# controller.net
KiCad netlist of a schematic drawn in EAGLE
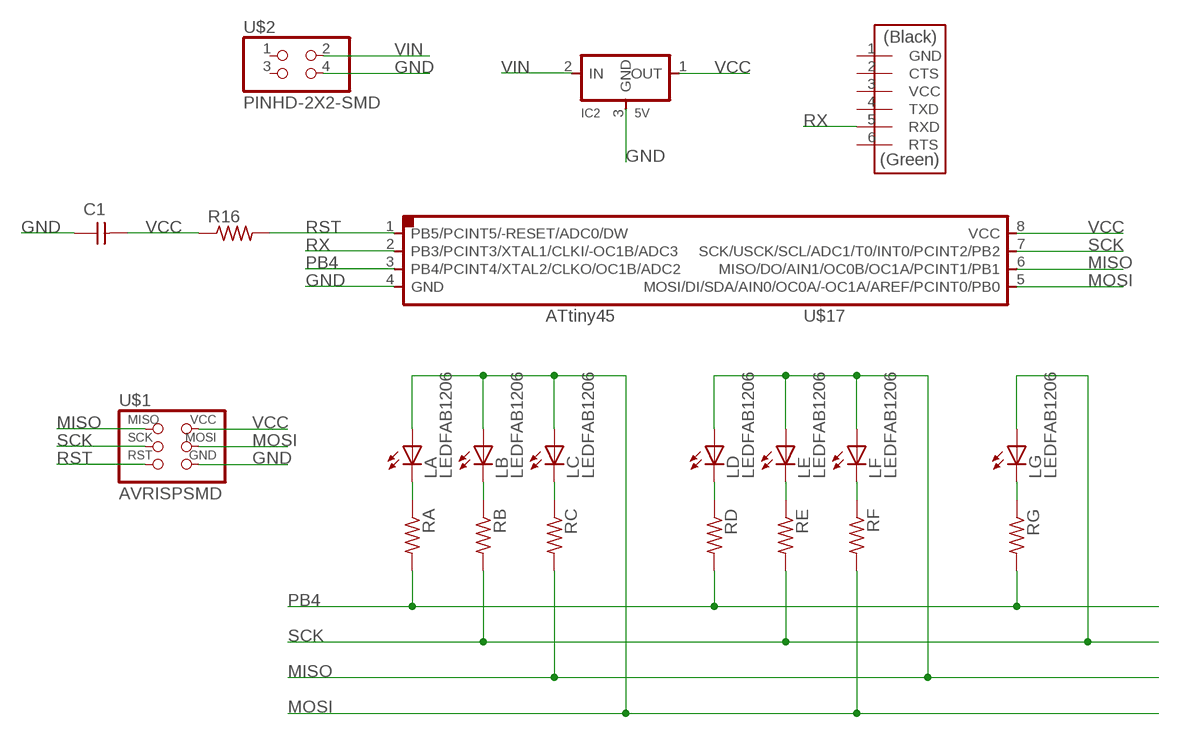
[diagram p0: schematic, sheet 1]

(export (version "E")
  (design (tool "Eeschema 10.0.6"))
  (components
    (comp (ref "C1")
      (value "CAP-UNPOLARIZEDFAB")
      (footprint "eagle-import:C1206FAB")
      (libsource (lib "eagle-import") (part "CAP-UNPOLARIZEDFAB"))
    )
    (comp (ref "IC2")
      (value "5V")
      (footprint "eagle-import:SOT23")
      (libsource (lib "eagle-import") (part "REGULATORSOT23"))
    )
    (comp (ref "LA")
      (value "LEDFAB1206")
      (footprint "eagle-import:LED1206FAB")
      (libsource (lib "eagle-import") (part "LEDFAB1206"))
    )
    (comp (ref "LB")
      (value "LEDFAB1206")
      (footprint "eagle-import:LED1206FAB")
      (libsource (lib "eagle-import") (part "LEDFAB1206"))
    )
    (comp (ref "LC")
      (value "LEDFAB1206")
      (footprint "eagle-import:LED1206FAB")
      (libsource (lib "eagle-import") (part "LEDFAB1206"))
    )
    (comp (ref "LD")
      (value "LEDFAB1206")
      (footprint "eagle-import:LED1206FAB")
      (libsource (lib "eagle-import") (part "LEDFAB1206"))
    )
    (comp (ref "LE")
      (value "LEDFAB1206")
      (footprint "eagle-import:LED1206FAB")
      (libsource (lib "eagle-import") (part "LEDFAB1206"))
    )
    (comp (ref "LF")
      (value "LEDFAB1206")
      (footprint "eagle-import:LED1206FAB")
      (libsource (lib "eagle-import") (part "LEDFAB1206"))
    )
    (comp (ref "LG")
      (value "LEDFAB1206")
      (footprint "eagle-import:LED1206FAB")
      (libsource (lib "eagle-import") (part "LEDFAB1206"))
    )
    (comp (ref "R16")
      (value "RES-US1206FAB")
      (footprint "eagle-import:R1206FAB")
      (libsource (lib "eagle-import") (part "RES-US1206FAB"))
    )
    (comp (ref "RA")
      (value "RES-US1206FAB")
      (footprint "eagle-import:R1206FAB")
      (libsource (lib "eagle-import") (part "RES-US1206FAB"))
    )
    (comp (ref "RB")
      (value "RES-US1206FAB")
      (footprint "eagle-import:R1206FAB")
      (libsource (lib "eagle-import") (part "RES-US1206FAB"))
    )
    (comp (ref "RC")
      (value "RES-US1206FAB")
      (footprint "eagle-import:R1206FAB")
      (libsource (lib "eagle-import") (part "RES-US1206FAB"))
    )
    (comp (ref "RD")
      (value "RES-US1206FAB")
      (footprint "eagle-import:R1206FAB")
      (libsource (lib "eagle-import") (part "RES-US1206FAB"))
    )
    (comp (ref "RE")
      (value "RES-US1206FAB")
      (footprint "eagle-import:R1206FAB")
      (libsource (lib "eagle-import") (part "RES-US1206FAB"))
    )
    (comp (ref "RF")
      (value "RES-US1206FAB")
      (footprint "eagle-import:R1206FAB")
      (libsource (lib "eagle-import") (part "RES-US1206FAB"))
    )
    (comp (ref "RG")
      (value "RES-US1206FAB")
      (footprint "eagle-import:R1206FAB")
      (libsource (lib "eagle-import") (part "RES-US1206FAB"))
    )
    (comp (ref "U$1")
      (value "AVRISPSMD")
      (footprint "eagle-import:2X03SMD")
      (libsource (lib "eagle-import") (part "AVRISPSMD"))
    )
    (comp (ref "U$2")
      (value "PINHD-2X2-SMD")
      (footprint "eagle-import:2X02SMD")
      (libsource (lib "eagle-import") (part "PINHD-2X2-SMD"))
    )
    (comp (ref "U$3")
      (value "FTDI-SMD-HEADER")
      (footprint "eagle-import:1X06SMD")
      (libsource (lib "eagle-import") (part "FTDI-SMD-HEADER"))
    )
    (comp (ref "U$17")
      (value "ATTINY45SI")
      (footprint "eagle-import:SOIC8")
      (libsource (lib "eagle-import") (part "ATTINY45SI"))
    )
  )
  (nets
    (net (code "1") (name "/GND") (class "Default")
      (node (ref "C1") (pin "1") (pinfunction "1_1") (pintype "passive"))
      (node (ref "IC2") (pin "3") (pinfunction "GND_3") (pintype "bidirectional"))
      (node (ref "U$1") (pin "6") (pinfunction "GND_6") (pintype "passive"))
      (node (ref "U$17") (pin "4") (pinfunction "GND_4") (pintype "bidirectional"))
      (node (ref "U$2") (pin "4") (pinfunction "4_4") (pintype "passive"))
    )
    (net (code "2") (name "/MISO") (class "Default")
      (node (ref "LD") (pin "1") (pinfunction "A_1") (pintype "passive"))
      (node (ref "LE") (pin "1") (pinfunction "A_1") (pintype "passive"))
      (node (ref "LF") (pin "1") (pinfunction "A_1") (pintype "passive"))
      (node (ref "RC") (pin "2") (pinfunction "2_2") (pintype "passive"))
      (node (ref "U$1") (pin "1") (pinfunction "MISO_1") (pintype "passive"))
      (node (ref "U$17") (pin "6") (pinfunction "MISO/DO/AIN1/OC0B/OC1A/PCINT1/PB1_6") (pintype "bidirectional"))
    )
    (net (code "3") (name "/MOSI") (class "Default")
      (node (ref "LA") (pin "1") (pinfunction "A_1") (pintype "passive"))
      (node (ref "LB") (pin "1") (pinfunction "A_1") (pintype "passive"))
      (node (ref "LC") (pin "1") (pinfunction "A_1") (pintype "passive"))
      (node (ref "RF") (pin "2") (pinfunction "2_2") (pintype "passive"))
      (node (ref "U$1") (pin "4") (pinfunction "MOSI_4") (pintype "passive"))
      (node (ref "U$17") (pin "5") (pinfunction "MOSI/DI/SDA/AIN0/OC0A/-OC1A/AREF/PCINT0/PB0_5") (pintype "bidirectional"))
    )
    (net (code "4") (name "/PB4") (class "Default")
      (node (ref "RA") (pin "2") (pinfunction "2_2") (pintype "passive"))
      (node (ref "RD") (pin "2") (pinfunction "2_2") (pintype "passive"))
      (node (ref "RG") (pin "2") (pinfunction "2_2") (pintype "passive"))
      (node (ref "U$17") (pin "3") (pinfunction "PB4/PCINT4/XTAL2/CLKO/OC1B/ADC2_3") (pintype "bidirectional"))
    )
    (net (code "5") (name "/RST") (class "Default")
      (node (ref "R16") (pin "2") (pinfunction "2_2") (pintype "passive"))
      (node (ref "U$1") (pin "5") (pinfunction "RST_5") (pintype "passive"))
      (node (ref "U$17") (pin "1") (pinfunction "PB5/PCINT5/-RESET/ADC0/DW_1") (pintype "bidirectional"))
    )
    (net (code "6") (name "/RX") (class "Default")
      (node (ref "U$17") (pin "2") (pinfunction "PB3/PCINT3/XTAL1/CLKI/-OC1B/ADC3_2") (pintype "bidirectional"))
      (node (ref "U$3") (pin "5") (pinfunction "RXD_5") (pintype "bidirectional"))
    )
    (net (code "7") (name "/SCK") (class "Default")
      (node (ref "LG") (pin "1") (pinfunction "A_1") (pintype "passive"))
      (node (ref "RB") (pin "2") (pinfunction "2_2") (pintype "passive"))
      (node (ref "RE") (pin "2") (pinfunction "2_2") (pintype "passive"))
      (node (ref "U$1") (pin "3") (pinfunction "SCK_3") (pintype "passive"))
      (node (ref "U$17") (pin "7") (pinfunction "SCK/USCK/SCL/ADC1/T0/INT0/PCINT2/PB2_7") (pintype "bidirectional"))
    )
    (net (code "8") (name "/VCC") (class "Default")
      (node (ref "C1") (pin "2") (pinfunction "2_2") (pintype "passive"))
      (node (ref "IC2") (pin "1") (pinfunction "OUT_1") (pintype "bidirectional"))
      (node (ref "R16") (pin "1") (pinfunction "1_1") (pintype "passive"))
      (node (ref "U$1") (pin "2") (pinfunction "VCC_2") (pintype "passive"))
      (node (ref "U$17") (pin "8") (pinfunction "VCC_8") (pintype "bidirectional"))
    )
    (net (code "9") (name "/VIN") (class "Default")
      (node (ref "IC2") (pin "2") (pinfunction "IN_2") (pintype "bidirectional"))
      (node (ref "U$2") (pin "2") (pinfunction "2_2") (pintype "passive"))
    )
    (net (code "10") (name "Net-(LA-C)") (class "Default")
      (node (ref "LA") (pin "2") (pinfunction "C_2") (pintype "passive"))
      (node (ref "RA") (pin "1") (pinfunction "1_1") (pintype "passive"))
    )
    (net (code "11") (name "Net-(LB-C)") (class "Default")
      (node (ref "LB") (pin "2") (pinfunction "C_2") (pintype "passive"))
      (node (ref "RB") (pin "1") (pinfunction "1_1") (pintype "passive"))
    )
    (net (code "12") (name "Net-(LC-C)") (class "Default")
      (node (ref "LC") (pin "2") (pinfunction "C_2") (pintype "passive"))
      (node (ref "RC") (pin "1") (pinfunction "1_1") (pintype "passive"))
    )
    (net (code "13") (name "Net-(LD-C)") (class "Default")
      (node (ref "LD") (pin "2") (pinfunction "C_2") (pintype "passive"))
      (node (ref "RD") (pin "1") (pinfunction "1_1") (pintype "passive"))
    )
    (net (code "14") (name "Net-(LE-C)") (class "Default")
      (node (ref "LE") (pin "2") (pinfunction "C_2") (pintype "passive"))
      (node (ref "RE") (pin "1") (pinfunction "1_1") (pintype "passive"))
    )
    (net (code "15") (name "Net-(LF-C)") (class "Default")
      (node (ref "LF") (pin "2") (pinfunction "C_2") (pintype "passive"))
      (node (ref "RF") (pin "1") (pinfunction "1_1") (pintype "passive"))
    )
    (net (code "16") (name "Net-(LG-C)") (class "Default")
      (node (ref "LG") (pin "2") (pinfunction "C_2") (pintype "passive"))
      (node (ref "RG") (pin "1") (pinfunction "1_1") (pintype "passive"))
    )
    (net (code "17") (name "unconnected-(U$2-Pad1)") (class "Default")
      (node (ref "U$2") (pin "1") (pinfunction "1_1") (pintype "passive"))
    )
    (net (code "18") (name "unconnected-(U$2-Pad3)") (class "Default")
      (node (ref "U$2") (pin "3") (pinfunction "3_3") (pintype "passive"))
    )
    (net (code "19") (name "unconnected-(U$3-CTS-Pad2)") (class "Default")
      (node (ref "U$3") (pin "2") (pinfunction "CTS_2") (pintype "bidirectional"))
    )
    (net (code "20") (name "unconnected-(U$3-GND-Pad1)") (class "Default")
      (node (ref "U$3") (pin "1") (pinfunction "GND_1") (pintype "bidirectional"))
    )
    (net (code "21") (name "unconnected-(U$3-RTS-Pad6)") (class "Default")
      (node (ref "U$3") (pin "6") (pinfunction "RTS_6") (pintype "bidirectional"))
    )
    (net (code "22") (name "unconnected-(U$3-TXD-Pad4)") (class "Default")
      (node (ref "U$3") (pin "4") (pinfunction "TXD_4") (pintype "bidirectional"))
    )
    (net (code "23") (name "unconnected-(U$3-VCC-Pad3)") (class "Default")
      (node (ref "U$3") (pin "3") (pinfunction "VCC_3") (pintype "bidirectional"))
    )
  )
)
